# Debug.net
KiCad netlist of a schematic drawn in Altium Designer
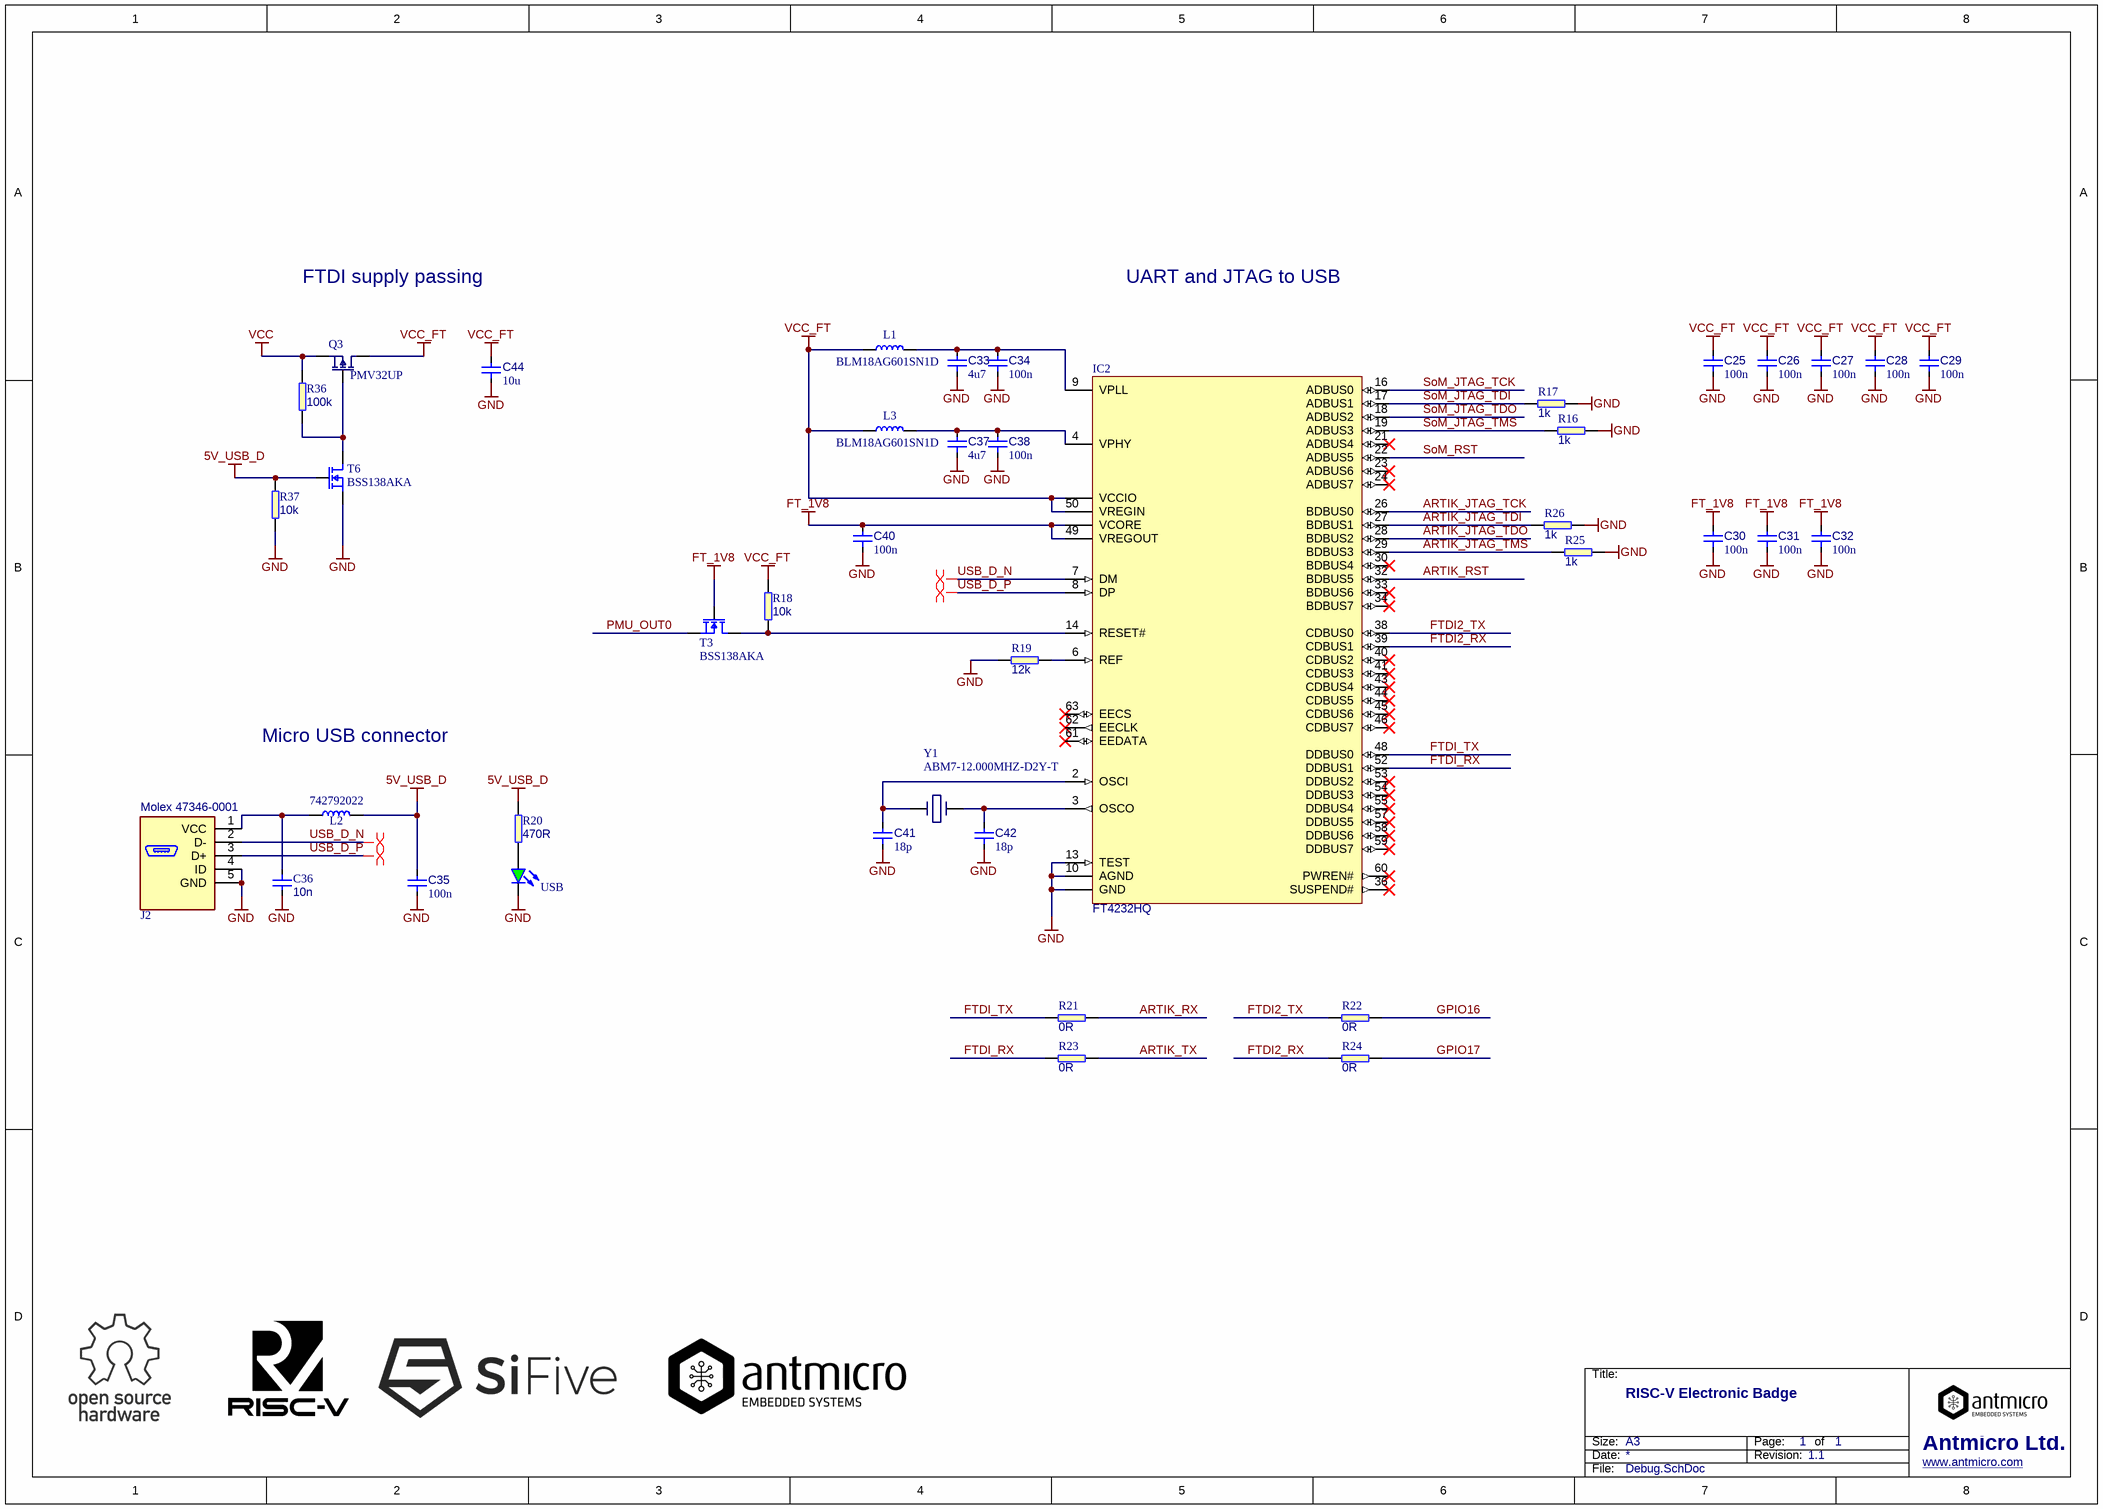
[diagram p0: Debug.SchDoc]

(export (version "E")
  (design (tool "Eeschema 10.0.6"))
  (components
    (comp (ref "C25")
      (value "100n")
      (footprint "0402")
      (description "MLCC SMT Capacitor 100nF 0402")
      (fields (field (name "PART NUMBER") "C_100n_0402") (field (name "MANUFACTURER") "MULTICOMP"))
      (libsource (lib "FE310_Badge") (part "C_100n_0402"))
    )
    (comp (ref "C26")
      (value "100n")
      (footprint "0402")
      (description "MLCC SMT Capacitor 100nF 0402")
      (fields (field (name "PART NUMBER") "C_100n_0402") (field (name "MANUFACTURER") "MULTICOMP"))
      (libsource (lib "FE310_Badge") (part "C_100n_0402"))
    )
    (comp (ref "C27")
      (value "100n")
      (footprint "0402")
      (description "MLCC SMT Capacitor 100nF 0402")
      (fields (field (name "PART NUMBER") "C_100n_0402") (field (name "MANUFACTURER") "MULTICOMP"))
      (libsource (lib "FE310_Badge") (part "C_100n_0402"))
    )
    (comp (ref "C28")
      (value "100n")
      (footprint "0402")
      (description "MLCC SMT Capacitor 100nF 0402")
      (fields (field (name "PART NUMBER") "C_100n_0402") (field (name "MANUFACTURER") "MULTICOMP"))
      (libsource (lib "FE310_Badge") (part "C_100n_0402"))
    )
    (comp (ref "C29")
      (value "100n")
      (footprint "0402")
      (description "MLCC SMT Capacitor 100nF 0402")
      (fields (field (name "PART NUMBER") "C_100n_0402") (field (name "MANUFACTURER") "MULTICOMP"))
      (libsource (lib "FE310_Badge") (part "C_100n_0402"))
    )
    (comp (ref "C30")
      (value "100n")
      (footprint "0402")
      (description "MLCC SMT Capacitor 100nF 0402")
      (fields (field (name "PART NUMBER") "C_100n_0402") (field (name "MANUFACTURER") "MULTICOMP"))
      (libsource (lib "FE310_Badge") (part "C_100n_0402"))
    )
    (comp (ref "C31")
      (value "100n")
      (footprint "0402")
      (description "MLCC SMT Capacitor 100nF 0402")
      (fields (field (name "PART NUMBER") "C_100n_0402") (field (name "MANUFACTURER") "MULTICOMP"))
      (libsource (lib "FE310_Badge") (part "C_100n_0402"))
    )
    (comp (ref "C32")
      (value "100n")
      (footprint "0402")
      (description "MLCC SMT Capacitor 100nF 0402")
      (fields (field (name "PART NUMBER") "C_100n_0402") (field (name "MANUFACTURER") "MULTICOMP"))
      (libsource (lib "FE310_Badge") (part "C_100n_0402"))
    )
    (comp (ref "C33")
      (value "4u7")
      (footprint "0402")
      (description "MLCC SMT Capacitor 4u7 0402")
      (fields (field (name "PART NUMBER") "C_4u7_0402") (field (name "MANUFACTURER") "MURATA"))
      (libsource (lib "FE310_Badge") (part "C_4u7_0402"))
    )
    (comp (ref "C34")
      (value "100n")
      (footprint "0402")
      (description "MLCC SMT Capacitor 100nF 0402")
      (fields (field (name "PART NUMBER") "C_100n_0402") (field (name "MANUFACTURER") "MULTICOMP"))
      (libsource (lib "FE310_Badge") (part "C_100n_0402"))
    )
    (comp (ref "C35")
      (value "100n")
      (footprint "0603")
      (description "MLCC SMT Capacitor 100nF 0603")
      (fields (field (name "PART NUMBER") "C_100n_0603") (field (name "MANUFACTURER") "WALSIN"))
      (libsource (lib "FE310_Badge") (part "C_100n_0603"))
    )
    (comp (ref "C36")
      (value "10n")
      (footprint "0603")
      (description "MLCC SMT Capacitor 10n 0603")
      (fields (field (name "PART NUMBER") "C_10n_0603") (field (name "MANUFACTURER") "AVX"))
      (libsource (lib "FE310_Badge") (part "C_10n_0603"))
    )
    (comp (ref "C37")
      (value "4u7")
      (footprint "0402")
      (description "MLCC SMT Capacitor 4u7 0402")
      (fields (field (name "PART NUMBER") "C_4u7_0402") (field (name "MANUFACTURER") "MURATA"))
      (libsource (lib "FE310_Badge") (part "C_4u7_0402"))
    )
    (comp (ref "C38")
      (value "100n")
      (footprint "0402")
      (description "MLCC SMT Capacitor 100nF 0402")
      (fields (field (name "PART NUMBER") "C_100n_0402") (field (name "MANUFACTURER") "MULTICOMP"))
      (libsource (lib "FE310_Badge") (part "C_100n_0402"))
    )
    (comp (ref "C40")
      (value "100n")
      (footprint "0402")
      (description "MLCC SMT Capacitor 100nF 0402")
      (fields (field (name "PART NUMBER") "C_100n_0402") (field (name "MANUFACTURER") "MULTICOMP"))
      (libsource (lib "FE310_Badge") (part "C_100n_0402"))
    )
    (comp (ref "C41")
      (value "18p")
      (footprint "0402")
      (description "MLCC SMT Capacitor 18pF 0402")
      (fields (field (name "PART NUMBER") "C_18p_0402") (field (name "MANUFACTURER") "KEMET"))
      (libsource (lib "FE310_Badge") (part "C_18p_0402"))
    )
    (comp (ref "C42")
      (value "18p")
      (footprint "0402")
      (description "MLCC SMT Capacitor 18pF 0402")
      (fields (field (name "PART NUMBER") "C_18p_0402") (field (name "MANUFACTURER") "KEMET"))
      (libsource (lib "FE310_Badge") (part "C_18p_0402"))
    )
    (comp (ref "C44")
      (value "10u")
      (footprint "0402")
      (description "MLCC SMT Capacitor 10uF 0402")
      (fields (field (name "PART NUMBER") "C_10u_0402") (field (name "MANUFACTURER") "TDK"))
      (libsource (lib "FE310_Badge") (part "C_10u_0402"))
    )
    (comp (ref "IC2")
      (value "FT4232HQ")
      (footprint "FT2232HQ")
      (description "FTDI  FT4232HQ-R  Interface Bridges, USB to UART, MPSSE, 1.62 V, 1.98 V, QFN, 64 Pins, -40 °C")
      (fields (field (name "MANUFACTURER") "FTDI"))
      (libsource (lib "FE310_Badge") (part "FT4232HQ"))
    )
    (comp (ref "J2")
      (value "Molex 47346-0001")
      (footprint "CON-Molex-047346-0001")
      (description "USB - micro B Receptacle Connector 5 Position Surface Mount, Right Angle, Horizontal")
      (fields (field (name "PART NUMBER") "CON-Molex-47346-0001") (field (name "MANUFACTURER") "Molex"))
      (libsource (lib "FE310_Badge") (part "Micro USB B"))
    )
    (comp (ref "L1")
      (value "BLM18AG601SN1D")
      (footprint "0603")
      (description "Ferrite Bead, 600 ohm, 0603 [1608 Metric], BLM18A Series, 500 mA, 0.38 ohm, ± 25%")
      (fields (field (name "MANUFACTURER") "MURATA"))
      (libsource (lib "FE310_Badge") (part "Inductor SMT_0603"))
    )
    (comp (ref "L2")
      (value "742792022")
      (footprint "0805")
      (description "WURTH ELEKTRONIK - 742792022 - FERRITE BEAD, 0.05OHM, 2A, 0805")
      (fields (field (name "MANUFACTURER") "WURTH ELEKTRONIK"))
      (libsource (lib "FE310_Badge") (part "Inductor SMT_0805"))
    )
    (comp (ref "L3")
      (value "BLM18AG601SN1D")
      (footprint "0603")
      (description "Ferrite Bead, 600 ohm, 0603 [1608 Metric], BLM18A Series, 500 mA, 0.38 ohm, ± 25%")
      (fields (field (name "MANUFACTURER") "MURATA"))
      (libsource (lib "FE310_Badge") (part "Inductor SMT_0603"))
    )
    (comp (ref "Q3")
      (value "PMV32UP")
      (footprint "SOT-23")
      (description "P CH, 20V, 4A")
      (fields (field (name "MANUFACTURER") "NXP"))
      (libsource (lib "FE310_Badge") (part "PMOS"))
    )
    (comp (ref "R16")
      (value "1k")
      (footprint "0402")
      (description "RES, 1k, 0402")
      (fields (field (name "PART NUMBER") "R_1k_0402") (field (name "MANUFACTURER") "MULTICOMP"))
      (libsource (lib "FE310_Badge") (part "R_1k_0402"))
    )
    (comp (ref "R17")
      (value "1k")
      (footprint "0402")
      (description "RES, 1k, 0402")
      (fields (field (name "PART NUMBER") "R_1k_0402") (field (name "MANUFACTURER") "MULTICOMP"))
      (libsource (lib "FE310_Badge") (part "R_1k_0402"))
    )
    (comp (ref "R18")
      (value "10k")
      (footprint "0402")
      (description "RES, 10k, 0402")
      (fields (field (name "PART NUMBER") "R_10k_0402") (field (name "MANUFACTURER") "MULTICOMP"))
      (libsource (lib "FE310_Badge") (part "R_10k_0402"))
    )
    (comp (ref "R19")
      (value "12k")
      (footprint "0402")
      (description "RES, 12k 0402")
      (fields (field (name "PART NUMBER") "R_12k_0402") (field (name "MANUFACTURER") "VISHAY"))
      (libsource (lib "FE310_Badge") (part "R_12k_0402"))
    )
    (comp (ref "R20")
      (value "470R")
      (footprint "0603")
      (description "RES, 470R, 0603")
      (fields (field (name "PART NUMBER") "R_470R_0603") (field (name "MANUFACTURER") "BOURNS"))
      (libsource (lib "FE310_Badge") (part "R_470R_0603"))
    )
    (comp (ref "R21")
      (value "0R")
      (footprint "0603")
      (description "RES, 0R, 0603")
      (fields (field (name "PART NUMBER") "R_0R_0603") (field (name "MANUFACTURER") "BOURNS"))
      (libsource (lib "FE310_Badge") (part "R_0R_0603"))
    )
    (comp (ref "R22")
      (value "0R")
      (footprint "0603")
      (description "RES, 0R, 0603")
      (fields (field (name "PART NUMBER") "R_0R_0603") (field (name "MANUFACTURER") "BOURNS"))
      (libsource (lib "FE310_Badge") (part "R_0R_0603"))
    )
    (comp (ref "R23")
      (value "0R")
      (footprint "0603")
      (description "RES, 0R, 0603")
      (fields (field (name "PART NUMBER") "R_0R_0603") (field (name "MANUFACTURER") "BOURNS"))
      (libsource (lib "FE310_Badge") (part "R_0R_0603"))
    )
    (comp (ref "R24")
      (value "0R")
      (footprint "0603")
      (description "RES, 0R, 0603")
      (fields (field (name "PART NUMBER") "R_0R_0603") (field (name "MANUFACTURER") "BOURNS"))
      (libsource (lib "FE310_Badge") (part "R_0R_0603"))
    )
    (comp (ref "R25")
      (value "1k")
      (footprint "0402")
      (description "RES, 1k, 0402")
      (fields (field (name "PART NUMBER") "R_1k_0402") (field (name "MANUFACTURER") "MULTICOMP"))
      (libsource (lib "FE310_Badge") (part "R_1k_0402"))
    )
    (comp (ref "R26")
      (value "1k")
      (footprint "0402")
      (description "RES, 1k, 0402")
      (fields (field (name "PART NUMBER") "R_1k_0402") (field (name "MANUFACTURER") "MULTICOMP"))
      (libsource (lib "FE310_Badge") (part "R_1k_0402"))
    )
    (comp (ref "R36")
      (value "100k")
      (footprint "0402")
      (description "RES, 100k 0402")
      (fields (field (name "PART NUMBER") "R_100k_0402") (field (name "MANUFACTURER") "VISHAY"))
      (libsource (lib "FE310_Badge") (part "R_100k_0402"))
    )
    (comp (ref "R37")
      (value "10k")
      (footprint "0402")
      (description "RES, 10k, 0402")
      (fields (field (name "PART NUMBER") "R_10k_0402") (field (name "MANUFACTURER") "MULTICOMP"))
      (libsource (lib "FE310_Badge") (part "R_10k_0402"))
    )
    (comp (ref "T3")
      (value "BSS138AKA")
      (footprint "SOT-23")
      (description "MOSFET, N CH, 60V, 0.2A")
      (fields (field (name "PART NUMBER") "BSS138") (field (name "MANUFACTURER") "NXP"))
      (libsource (lib "FE310_Badge") (part "NMOS"))
    )
    (comp (ref "T6")
      (value "BSS138AKA")
      (footprint "SOT-23")
      (description "MOSFET, N CH, 60V, 0.2A")
      (fields (field (name "PART NUMBER") "BSS138") (field (name "MANUFACTURER") "NXP"))
      (libsource (lib "FE310_Badge") (part "NMOS"))
    )
    (comp (ref "USB")
      (value "KPT-1608SGC")
      (footprint "LED0603")
      (description "LED Green 0603 case")
      (fields (field (name "PART NUMBER") "LED_G") (field (name "MANUFACTURER") "KINGBRIGHT"))
      (libsource (lib "FE310_Badge") (part "LED"))
    )
    (comp (ref "Y1")
      (value "ABM7-12.000MHZ-D2Y-T")
      (footprint "abm7")
      (description "CRYSTAL, 12MHZ, 18PF, SMD")
      (fields
        (field (name "PART NUMBER") "CRYSTAL_12MHz_SMD_6.0x3.5mm")
        (field (name "MANUFACTURER") "ABRACON")
      )
      (libsource (lib "FE310_Badge") (part "CRYSTAL"))
    )
  )
  (nets
    (net (code "1") (name "/ARTIK_JTAG_TCK") (class "Default")
      (node (ref "IC2") (pin "26") (pinfunction "BDBUS0_26") (pintype "bidirectional"))
    )
    (net (code "2") (name "/ARTIK_JTAG_TDI") (class "Default")
      (node (ref "IC2") (pin "27") (pinfunction "BDBUS1_27") (pintype "bidirectional"))
      (node (ref "R26") (pin "2") (pintype "passive"))
    )
    (net (code "3") (name "/ARTIK_JTAG_TDO") (class "Default")
      (node (ref "IC2") (pin "28") (pinfunction "BDBUS2_28") (pintype "bidirectional"))
    )
    (net (code "4") (name "/ARTIK_JTAG_TMS") (class "Default")
      (node (ref "IC2") (pin "29") (pinfunction "BDBUS3_29") (pintype "bidirectional"))
      (node (ref "R25") (pin "2") (pintype "passive"))
    )
    (net (code "5") (name "/ARTIK_RST") (class "Default")
      (node (ref "IC2") (pin "32") (pinfunction "BDBUS5_32") (pintype "bidirectional"))
    )
    (net (code "6") (name "/ARTIK_RX") (class "Default") (node (ref "R21") (pin "2") (pintype "passive")))
    (net (code "7") (name "/ARTIK_TX") (class "Default") (node (ref "R23") (pin "2") (pintype "passive")))
    (net (code "8") (name "/FTDI2_RX") (class "Default")
      (node (ref "IC2") (pin "39") (pinfunction "CDBUS1_39") (pintype "bidirectional"))
      (node (ref "R24") (pin "1") (pintype "passive"))
    )
    (net (code "9") (name "/FTDI2_TX") (class "Default")
      (node (ref "IC2") (pin "38") (pinfunction "CDBUS0_38") (pintype "bidirectional"))
      (node (ref "R22") (pin "1") (pintype "passive"))
    )
    (net (code "10") (name "/FTDI_RX") (class "Default")
      (node (ref "IC2") (pin "52") (pinfunction "DDBUS1_52") (pintype "bidirectional"))
      (node (ref "R23") (pin "1") (pintype "passive"))
    )
    (net (code "11") (name "/FTDI_TX") (class "Default")
      (node (ref "IC2") (pin "48") (pinfunction "DDBUS0_48") (pintype "bidirectional"))
      (node (ref "R21") (pin "1") (pintype "passive"))
    )
    (net (code "12") (name "/GPIO16") (class "Default") (node (ref "R22") (pin "2") (pintype "passive")))
    (net (code "13") (name "/GPIO17") (class "Default") (node (ref "R24") (pin "2") (pintype "passive")))
    (net (code "14") (name "/PMU_OUT0") (class "Default")
      (node (ref "T3") (pin "2") (pinfunction "S_2") (pintype "passive"))
    )
    (net (code "15") (name "/SoM_JTAG_TCK") (class "Default")
      (node (ref "IC2") (pin "16") (pinfunction "ADBUS0_16") (pintype "bidirectional"))
    )
    (net (code "16") (name "/SoM_JTAG_TDI") (class "Default")
      (node (ref "IC2") (pin "17") (pinfunction "ADBUS1_17") (pintype "bidirectional"))
      (node (ref "R17") (pin "2") (pintype "passive"))
    )
    (net (code "17") (name "/SoM_JTAG_TDO") (class "Default")
      (node (ref "IC2") (pin "18") (pinfunction "ADBUS2_18") (pintype "bidirectional"))
    )
    (net (code "18") (name "/SoM_JTAG_TMS") (class "Default")
      (node (ref "IC2") (pin "19") (pinfunction "ADBUS3_19") (pintype "bidirectional"))
      (node (ref "R16") (pin "2") (pintype "passive"))
    )
    (net (code "19") (name "/SoM_RST") (class "Default")
      (node (ref "IC2") (pin "22") (pinfunction "ADBUS5_22") (pintype "bidirectional"))
    )
    (net (code "20") (name "/USB_D_N") (class "Default")
      (node (ref "IC2") (pin "7") (pinfunction "DM_7") (pintype "input"))
      (node (ref "J2") (pin "2") (pinfunction "D-_2") (pintype "passive"))
    )
    (net (code "21") (name "/USB_D_P") (class "Default")
      (node (ref "IC2") (pin "8") (pinfunction "DP_8") (pintype "input"))
      (node (ref "J2") (pin "3") (pinfunction "D+_3") (pintype "passive"))
    )
    (net (code "22") (name "5V_USB_D") (class "Default")
      (node (ref "C35") (pin "2") (pinfunction "2_2") (pintype "passive"))
      (node (ref "L2") (pin "1") (pintype "passive"))
      (node (ref "R20") (pin "2") (pintype "passive"))
      (node (ref "R37") (pin "1") (pintype "passive"))
      (node (ref "T6") (pin "1") (pinfunction "G_1") (pintype "passive"))
    )
    (net (code "23") (name "FT_1V8") (class "Default")
      (node (ref "C30") (pin "2") (pinfunction "2_2") (pintype "passive"))
      (node (ref "C31") (pin "2") (pinfunction "2_2") (pintype "passive"))
      (node (ref "C32") (pin "2") (pinfunction "2_2") (pintype "passive"))
      (node (ref "C40") (pin "2") (pinfunction "2_2") (pintype "passive"))
      (node (ref "IC2") (pin "49") (pinfunction "VREGOUT_49") (pintype "power_in"))
      (node (ref "IC2") (pin "VCORE") (pinfunction "VCORE_VCORE") (pintype "power_in"))
      (node (ref "T3") (pin "1") (pinfunction "G_1") (pintype "passive"))
    )
    (net (code "24") (name "GND") (class "Default")
      (node (ref "C25") (pin "1") (pinfunction "1_1") (pintype "passive"))
      (node (ref "C26") (pin "1") (pinfunction "1_1") (pintype "passive"))
      (node (ref "C27") (pin "1") (pinfunction "1_1") (pintype "passive"))
      (node (ref "C28") (pin "1") (pinfunction "1_1") (pintype "passive"))
      (node (ref "C29") (pin "1") (pinfunction "1_1") (pintype "passive"))
      (node (ref "C30") (pin "1") (pinfunction "1_1") (pintype "passive"))
      (node (ref "C31") (pin "1") (pinfunction "1_1") (pintype "passive"))
      (node (ref "C32") (pin "1") (pinfunction "1_1") (pintype "passive"))
      (node (ref "C33") (pin "1") (pinfunction "1_1") (pintype "passive"))
      (node (ref "C34") (pin "1") (pinfunction "1_1") (pintype "passive"))
      (node (ref "C35") (pin "1") (pinfunction "1_1") (pintype "passive"))
      (node (ref "C36") (pin "2") (pinfunction "2_2") (pintype "passive"))
      (node (ref "C37") (pin "1") (pinfunction "1_1") (pintype "passive"))
      (node (ref "C38") (pin "1") (pinfunction "1_1") (pintype "passive"))
      (node (ref "C40") (pin "1") (pinfunction "1_1") (pintype "passive"))
      (node (ref "C41") (pin "1") (pinfunction "1_1") (pintype "passive"))
      (node (ref "C42") (pin "1") (pinfunction "1_1") (pintype "passive"))
      (node (ref "C44") (pin "1") (pinfunction "1_1") (pintype "passive"))
      (node (ref "IC2") (pin "10") (pinfunction "AGND_10") (pintype "power_in"))
      (node (ref "IC2") (pin "13") (pinfunction "TEST_13") (pintype "input"))
      (node (ref "IC2") (pin "GND") (pinfunction "GND_GND") (pintype "power_in"))
      (node (ref "J2") (pin "4") (pinfunction "ID_4") (pintype "passive"))
      (node (ref "J2") (pin "5") (pinfunction "GND_5") (pintype "power_in"))
      (node (ref "R16") (pin "1") (pintype "passive"))
      (node (ref "R17") (pin "1") (pintype "passive"))
      (node (ref "R19") (pin "1") (pintype "passive"))
      (node (ref "R25") (pin "1") (pintype "passive"))
      (node (ref "R26") (pin "1") (pintype "passive"))
      (node (ref "R37") (pin "2") (pintype "passive"))
      (node (ref "T6") (pin "2") (pinfunction "S_2") (pintype "passive"))
      (node (ref "USB") (pin "K") (pinfunction "K_K") (pintype "passive"))
    )
    (net (code "25") (name "Net-(IC2-OSCI)") (class "Default")
      (node (ref "C41") (pin "2") (pinfunction "2_2") (pintype "passive"))
      (node (ref "IC2") (pin "2") (pinfunction "OSCI_2") (pintype "input"))
      (node (ref "Y1") (pin "2") (pinfunction "2_2") (pintype "passive"))
    )
    (net (code "26") (name "Net-(IC2-OSCO)") (class "Default")
      (node (ref "C42") (pin "2") (pinfunction "2_2") (pintype "passive"))
      (node (ref "IC2") (pin "3") (pinfunction "OSCO_3") (pintype "output"))
      (node (ref "Y1") (pin "1") (pinfunction "1_1") (pintype "passive"))
    )
    (net (code "27") (name "Net-(IC2-REF)") (class "Default")
      (node (ref "IC2") (pin "6") (pinfunction "REF_6") (pintype "input"))
      (node (ref "R19") (pin "2") (pintype "passive"))
    )
    (net (code "28") (name "Net-(IC2-RESET#)") (class "Default")
      (node (ref "IC2") (pin "14") (pinfunction "RESET#_14") (pintype "input"))
      (node (ref "R18") (pin "2") (pintype "passive"))
      (node (ref "T3") (pin "3") (pinfunction "D_3") (pintype "passive"))
    )
    (net (code "29") (name "Net-(IC2-VPHY)") (class "Default")
      (node (ref "C37") (pin "2") (pinfunction "2_2") (pintype "passive"))
      (node (ref "C38") (pin "2") (pinfunction "2_2") (pintype "passive"))
      (node (ref "IC2") (pin "4") (pinfunction "VPHY_4") (pintype "power_in"))
      (node (ref "L3") (pin "2") (pintype "passive"))
    )
    (net (code "30") (name "Net-(IC2-VPLL)") (class "Default")
      (node (ref "C33") (pin "2") (pinfunction "2_2") (pintype "passive"))
      (node (ref "C34") (pin "2") (pinfunction "2_2") (pintype "passive"))
      (node (ref "IC2") (pin "9") (pinfunction "VPLL_9") (pintype "power_in"))
      (node (ref "L1") (pin "2") (pintype "passive"))
    )
    (net (code "31") (name "Net-(J2-VCC)") (class "Default")
      (node (ref "C36") (pin "1") (pinfunction "1_1") (pintype "passive"))
      (node (ref "J2") (pin "1") (pinfunction "VCC_1") (pintype "power_in"))
      (node (ref "L2") (pin "2") (pintype "passive"))
    )
    (net (code "32") (name "Net-(Q3-G)") (class "Default")
      (node (ref "Q3") (pin "1") (pinfunction "G_1") (pintype "passive"))
      (node (ref "R36") (pin "1") (pintype "passive"))
      (node (ref "T6") (pin "3") (pinfunction "D_3") (pintype "passive"))
    )
    (net (code "33") (name "Net-(R20-Pad1)") (class "Default")
      (node (ref "R20") (pin "1") (pintype "passive"))
      (node (ref "USB") (pin "A") (pinfunction "A_A") (pintype "passive"))
    )
    (net (code "34") (name "VCC") (class "Default")
      (node (ref "Q3") (pin "2") (pinfunction "S_2") (pintype "passive"))
      (node (ref "R36") (pin "2") (pintype "passive"))
    )
    (net (code "35") (name "VCC_FT") (class "Default")
      (node (ref "C25") (pin "2") (pinfunction "2_2") (pintype "passive"))
      (node (ref "C26") (pin "2") (pinfunction "2_2") (pintype "passive"))
      (node (ref "C27") (pin "2") (pinfunction "2_2") (pintype "passive"))
      (node (ref "C28") (pin "2") (pinfunction "2_2") (pintype "passive"))
      (node (ref "C29") (pin "2") (pinfunction "2_2") (pintype "passive"))
      (node (ref "C44") (pin "2") (pinfunction "2_2") (pintype "passive"))
      (node (ref "IC2") (pin "50") (pinfunction "VREGIN_50") (pintype "power_in"))
      (node (ref "IC2") (pin "VCCIO") (pinfunction "VCCIO_VCCIO") (pintype "power_in"))
      (node (ref "L1") (pin "1") (pintype "passive"))
      (node (ref "L3") (pin "1") (pintype "passive"))
      (node (ref "Q3") (pin "3") (pinfunction "D_3") (pintype "passive"))
      (node (ref "R18") (pin "1") (pintype "passive"))
    )
    (net (code "36") (name "unconnected-(IC2-ADBUS4-Pad21)") (class "Default")
      (node (ref "IC2") (pin "21") (pinfunction "ADBUS4_21") (pintype "bidirectional+no_connect"))
    )
    (net (code "37") (name "unconnected-(IC2-ADBUS6-Pad23)") (class "Default")
      (node (ref "IC2") (pin "23") (pinfunction "ADBUS6_23") (pintype "bidirectional+no_connect"))
    )
    (net (code "38") (name "unconnected-(IC2-ADBUS7-Pad24)") (class "Default")
      (node (ref "IC2") (pin "24") (pinfunction "ADBUS7_24") (pintype "bidirectional+no_connect"))
    )
    (net (code "39") (name "unconnected-(IC2-BDBUS4-Pad30)") (class "Default")
      (node (ref "IC2") (pin "30") (pinfunction "BDBUS4_30") (pintype "bidirectional+no_connect"))
    )
    (net (code "40") (name "unconnected-(IC2-BDBUS6-Pad33)") (class "Default")
      (node (ref "IC2") (pin "33") (pinfunction "BDBUS6_33") (pintype "bidirectional+no_connect"))
    )
    (net (code "41") (name "unconnected-(IC2-BDBUS7-Pad34)") (class "Default")
      (node (ref "IC2") (pin "34") (pinfunction "BDBUS7_34") (pintype "bidirectional+no_connect"))
    )
    (net (code "42") (name "unconnected-(IC2-CDBUS2-Pad40)") (class "Default")
      (node (ref "IC2") (pin "40") (pinfunction "CDBUS2_40") (pintype "bidirectional+no_connect"))
    )
    (net (code "43") (name "unconnected-(IC2-CDBUS3-Pad41)") (class "Default")
      (node (ref "IC2") (pin "41") (pinfunction "CDBUS3_41") (pintype "bidirectional+no_connect"))
    )
    (net (code "44") (name "unconnected-(IC2-CDBUS4-Pad43)") (class "Default")
      (node (ref "IC2") (pin "43") (pinfunction "CDBUS4_43") (pintype "bidirectional+no_connect"))
    )
    (net (code "45") (name "unconnected-(IC2-CDBUS5-Pad44)") (class "Default")
      (node (ref "IC2") (pin "44") (pinfunction "CDBUS5_44") (pintype "bidirectional+no_connect"))
    )
    (net (code "46") (name "unconnected-(IC2-CDBUS6-Pad45)") (class "Default")
      (node (ref "IC2") (pin "45") (pinfunction "CDBUS6_45") (pintype "bidirectional+no_connect"))
    )
    (net (code "47") (name "unconnected-(IC2-CDBUS7-Pad46)") (class "Default")
      (node (ref "IC2") (pin "46") (pinfunction "CDBUS7_46") (pintype "bidirectional+no_connect"))
    )
    (net (code "48") (name "unconnected-(IC2-DDBUS2-Pad53)") (class "Default")
      (node (ref "IC2") (pin "53") (pinfunction "DDBUS2_53") (pintype "bidirectional+no_connect"))
    )
    (net (code "49") (name "unconnected-(IC2-DDBUS3-Pad54)") (class "Default")
      (node (ref "IC2") (pin "54") (pinfunction "DDBUS3_54") (pintype "bidirectional+no_connect"))
    )
    (net (code "50") (name "unconnected-(IC2-DDBUS4-Pad55)") (class "Default")
      (node (ref "IC2") (pin "55") (pinfunction "DDBUS4_55") (pintype "bidirectional+no_connect"))
    )
    (net (code "51") (name "unconnected-(IC2-DDBUS5-Pad57)") (class "Default")
      (node (ref "IC2") (pin "57") (pinfunction "DDBUS5_57") (pintype "bidirectional+no_connect"))
    )
    (net (code "52") (name "unconnected-(IC2-DDBUS6-Pad58)") (class "Default")
      (node (ref "IC2") (pin "58") (pinfunction "DDBUS6_58") (pintype "bidirectional+no_connect"))
    )
    (net (code "53") (name "unconnected-(IC2-DDBUS7-Pad59)") (class "Default")
      (node (ref "IC2") (pin "59") (pinfunction "DDBUS7_59") (pintype "bidirectional+no_connect"))
    )
    (net (code "54") (name "unconnected-(IC2-EECLK-Pad62)") (class "Default")
      (node (ref "IC2") (pin "62") (pinfunction "EECLK_62") (pintype "output+no_connect"))
    )
    (net (code "55") (name "unconnected-(IC2-EECS-Pad63)") (class "Default")
      (node (ref "IC2") (pin "63") (pinfunction "EECS_63") (pintype "bidirectional+no_connect"))
    )
    (net (code "56") (name "unconnected-(IC2-EEDATA-Pad61)") (class "Default")
      (node (ref "IC2") (pin "61") (pinfunction "EEDATA_61") (pintype "bidirectional+no_connect"))
    )
    (net (code "57") (name "unconnected-(IC2-PWREN#-Pad60)") (class "Default")
      (node (ref "IC2") (pin "60") (pinfunction "PWREN#_60") (pintype "output+no_connect"))
    )
    (net (code "58") (name "unconnected-(IC2-SUSPEND#-Pad36)") (class "Default")
      (node (ref "IC2") (pin "36") (pinfunction "SUSPEND#_36") (pintype "output+no_connect"))
    )
  )
)
